# Hotend_Controller.net
KiCad netlist of a schematic drawn in Altium Designer
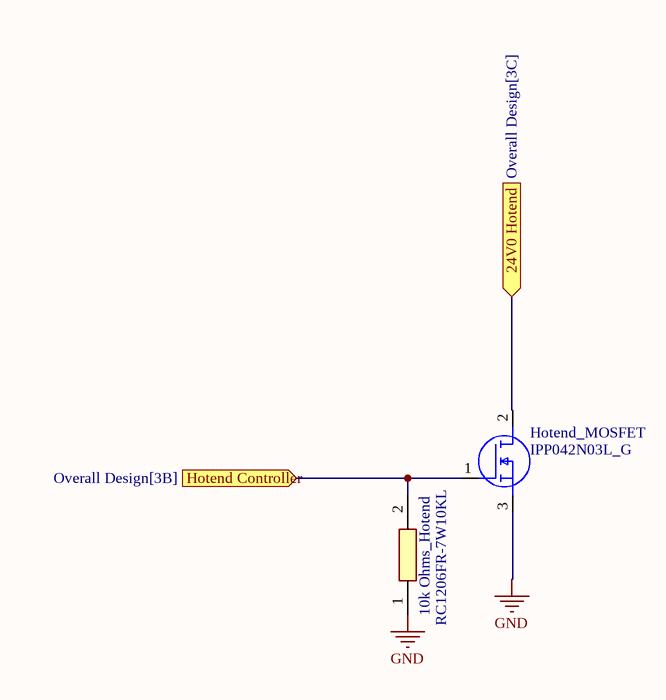
[diagram p0: Hotend Controller.SchDoc]

(export (version "E")
  (design (tool "Eeschema 10.0.6"))
  (components
    (comp (ref "10k Ohms_Hotend")
      (value "RC1206FR-7W10KL")
      (footprint "SamacSys:RESC3116X65N")
      (description "Resistor")
      (libsource (lib "*") (part "RC1206FR-7W10KL"))
    )
    (comp (ref "Hotend_MOSFET")
      (value "IPP042N03L_G")
      (footprint "SamacSys:TO254P457X1003X2115-3P")
      (description "MOSFET (N-Channel)")
      (fields
        (field (name "MANUFACTURER_PART_NUMBER") "IPP042N03L G")
        (field (name "MOUSER PART NUMBER") "726-IPP042N03LG")
      )
      (libsource (lib "*") (part "IPP042N03L_G"))
    )
  )
  (nets
    (net (code "1") (name "/24V0 Hotend") (class "Default")
      (node (ref "Hotend_MOSFET") (pin "2") (pinfunction "D_2") (pintype "passive"))
    )
    (net (code "2") (name "/Hotend Controller") (class "Default")
      (node (ref "10k Ohms_Hotend") (pin "2") (pinfunction "2_2") (pintype "passive"))
      (node (ref "Hotend_MOSFET") (pin "1") (pinfunction "G_1") (pintype "passive"))
    )
    (net (code "3") (name "GND") (class "Default")
      (node (ref "10k Ohms_Hotend") (pin "1") (pinfunction "1_1") (pintype "passive"))
      (node (ref "Hotend_MOSFET") (pin "3") (pinfunction "S_3") (pintype "passive"))
    )
  )
)
